# Enclosure_100x68_PBLPI.net
KiCad netlist of a schematic drawn in EAGLE
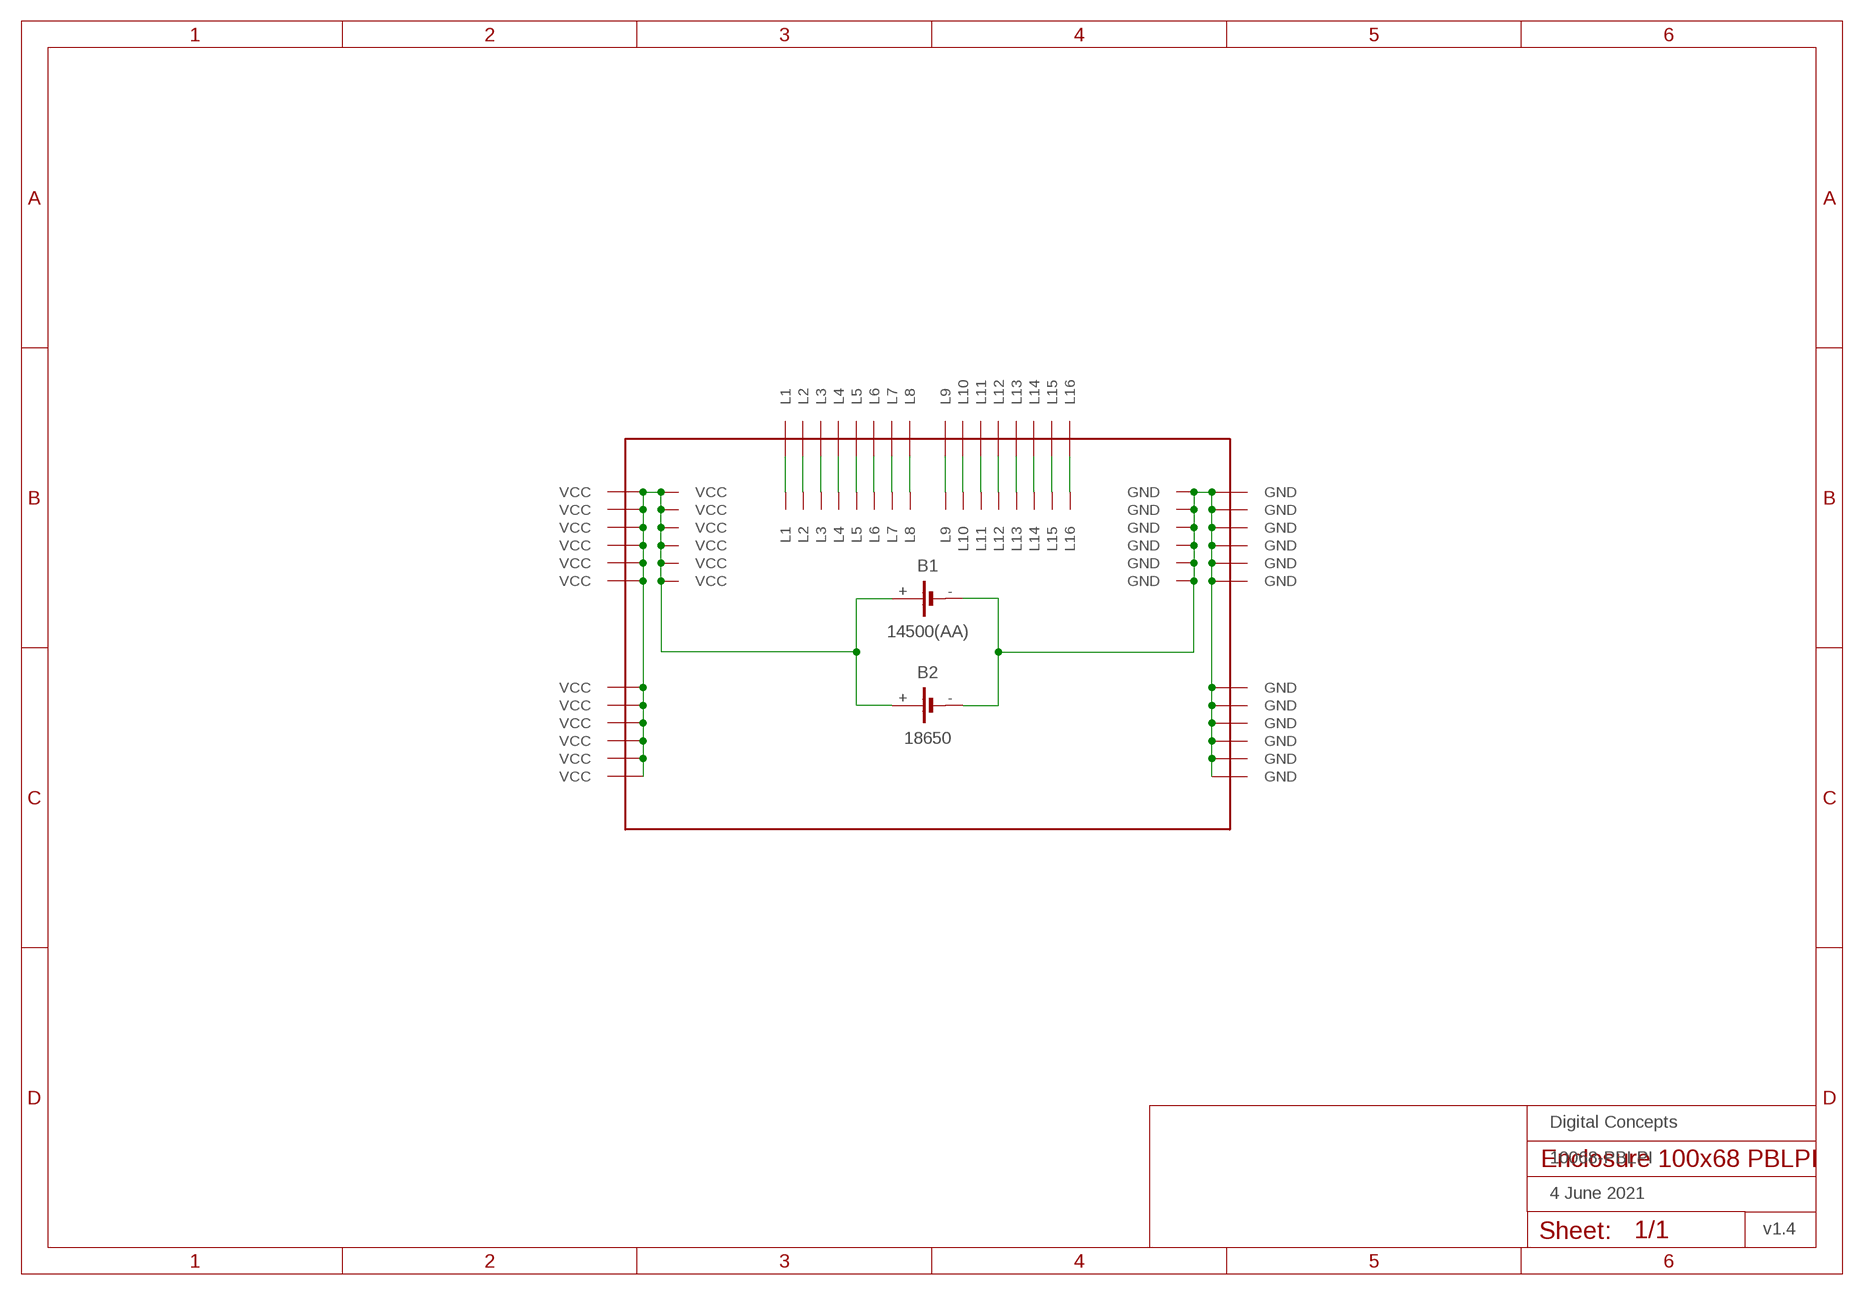
[diagram p0: schematic, sheet 1]

(export (version "E")
  (design (tool "Eeschema 10.0.6"))
  (components
    (comp (ref "B1")
      (value "14500(AA)")
      (footprint "eagle-import:BATTERY-14500")
      (libsource (lib "eagle-import") (part "BATTERY-HOLDER-14500(AA)"))
    )
    (comp (ref "B2")
      (value "18650")
      (footprint "eagle-import:BATTERY-18650")
      (libsource (lib "eagle-import") (part "BATTERY-HOLDER-18650"))
    )
    (comp (ref "P1")
      (value "PROTO-34X22-BAT-PI")
      (footprint "eagle-import:PROTO-34X22-BAT-PI")
      (libsource (lib "eagle-import") (part "PROTO-34X22-BAT-PI"))
    )
  )
  (nets
    (net (code "1") (name "Net-(B1-Pad+)") (class "Default")
      (node (ref "B1") (pin "+") (pinfunction "+_+") (pintype "power_in"))
      (node (ref "B2") (pin "+") (pinfunction "+_+") (pintype "power_in"))
      (node (ref "P1") (pin "P01-05") (pinfunction "VCC_P01-05") (pintype "power_in"))
      (node (ref "P1") (pin "P01-06") (pinfunction "VCC_P01-06") (pintype "power_in"))
      (node (ref "P1") (pin "P01-07") (pinfunction "VCC_P01-07") (pintype "power_in"))
      (node (ref "P1") (pin "P01-08") (pinfunction "VCC_P01-08") (pintype "power_in"))
      (node (ref "P1") (pin "P01-09") (pinfunction "VCC_P01-09") (pintype "power_in"))
      (node (ref "P1") (pin "P01-10") (pinfunction "VCC_P01-10") (pintype "power_in"))
      (node (ref "P1") (pin "P01-13") (pinfunction "VCC_P01-13") (pintype "power_in"))
      (node (ref "P1") (pin "P01-14") (pinfunction "VCC_P01-14") (pintype "power_in"))
      (node (ref "P1") (pin "P01-15") (pinfunction "VCC_P01-15") (pintype "power_in"))
      (node (ref "P1") (pin "P01-16") (pinfunction "VCC_P01-16") (pintype "power_in"))
      (node (ref "P1") (pin "P01-17") (pinfunction "VCC_P01-17") (pintype "power_in"))
      (node (ref "P1") (pin "P01-18") (pinfunction "VCC_P01-18") (pintype "power_in"))
      (node (ref "P1") (pin "P02-13") (pinfunction "VCC_P02-13") (pintype "power_in"))
      (node (ref "P1") (pin "P02-14") (pinfunction "VCC_P02-14") (pintype "power_in"))
      (node (ref "P1") (pin "P02-15") (pinfunction "VCC_P02-15") (pintype "power_in"))
      (node (ref "P1") (pin "P02-16") (pinfunction "VCC_P02-16") (pintype "power_in"))
      (node (ref "P1") (pin "P02-17") (pinfunction "VCC_P02-17") (pintype "power_in"))
      (node (ref "P1") (pin "P02-18") (pinfunction "VCC_P02-18") (pintype "power_in"))
    )
    (net (code "2") (name "Net-(B1-Pad-)") (class "Default")
      (node (ref "B1") (pin "-") (pinfunction "-_-") (pintype "power_in"))
      (node (ref "B2") (pin "-") (pinfunction "-_-") (pintype "power_in"))
      (node (ref "P1") (pin "P33-13") (pinfunction "GND_P33-13") (pintype "power_in"))
      (node (ref "P1") (pin "P33-14") (pinfunction "GND_P33-14") (pintype "power_in"))
      (node (ref "P1") (pin "P33-15") (pinfunction "GND_P33-15") (pintype "power_in"))
      (node (ref "P1") (pin "P33-16") (pinfunction "GND_P33-16") (pintype "power_in"))
      (node (ref "P1") (pin "P33-17") (pinfunction "GND_P33-17") (pintype "power_in"))
      (node (ref "P1") (pin "P33-18") (pinfunction "GND_P33-18") (pintype "power_in"))
      (node (ref "P1") (pin "P34-05") (pinfunction "GND_P34-05") (pintype "power_in"))
      (node (ref "P1") (pin "P34-06") (pinfunction "GND_P34-06") (pintype "power_in"))
      (node (ref "P1") (pin "P34-07") (pinfunction "GND_P34-07") (pintype "power_in"))
      (node (ref "P1") (pin "P34-08") (pinfunction "GND_P34-08") (pintype "power_in"))
      (node (ref "P1") (pin "P34-09") (pinfunction "GND_P34-09") (pintype "power_in"))
      (node (ref "P1") (pin "P34-10") (pinfunction "GND_P34-10") (pintype "power_in"))
      (node (ref "P1") (pin "P34-13") (pinfunction "GND_P34-13") (pintype "power_in"))
      (node (ref "P1") (pin "P34-14") (pinfunction "GND_P34-14") (pintype "power_in"))
      (node (ref "P1") (pin "P34-15") (pinfunction "GND_P34-15") (pintype "power_in"))
      (node (ref "P1") (pin "P34-16") (pinfunction "GND_P34-16") (pintype "power_in"))
      (node (ref "P1") (pin "P34-17") (pinfunction "GND_P34-17") (pintype "power_in"))
      (node (ref "P1") (pin "P34-18") (pinfunction "GND_P34-18") (pintype "power_in"))
    )
    (net (code "3") (name "Net-(P1-L1-PadP10-21)") (class "Default")
      (node (ref "P1") (pin "P10-21") (pinfunction "L1_P10-21") (pintype "passive"))
      (node (ref "P1") (pin "P10-22") (pinfunction "L1_P10-22") (pintype "passive"))
    )
    (net (code "4") (name "Net-(P1-L2-PadP11-21)") (class "Default")
      (node (ref "P1") (pin "P11-21") (pinfunction "L2_P11-21") (pintype "passive"))
      (node (ref "P1") (pin "P11-22") (pinfunction "L2_P11-22") (pintype "passive"))
    )
    (net (code "5") (name "Net-(P1-L3-PadP12-21)") (class "Default")
      (node (ref "P1") (pin "P12-21") (pinfunction "L3_P12-21") (pintype "passive"))
      (node (ref "P1") (pin "P12-22") (pinfunction "L3_P12-22") (pintype "passive"))
    )
    (net (code "6") (name "Net-(P1-L4-PadP13-21)") (class "Default")
      (node (ref "P1") (pin "P13-21") (pinfunction "L4_P13-21") (pintype "passive"))
      (node (ref "P1") (pin "P13-22") (pinfunction "L4_P13-22") (pintype "passive"))
    )
    (net (code "7") (name "Net-(P1-L5-PadP14-21)") (class "Default")
      (node (ref "P1") (pin "P14-21") (pinfunction "L5_P14-21") (pintype "passive"))
      (node (ref "P1") (pin "P14-22") (pinfunction "L5_P14-22") (pintype "passive"))
    )
    (net (code "8") (name "Net-(P1-L6-PadP15-21)") (class "Default")
      (node (ref "P1") (pin "P15-21") (pinfunction "L6_P15-21") (pintype "passive"))
      (node (ref "P1") (pin "P15-22") (pinfunction "L6_P15-22") (pintype "passive"))
    )
    (net (code "9") (name "Net-(P1-L7-PadP16-21)") (class "Default")
      (node (ref "P1") (pin "P16-21") (pinfunction "L7_P16-21") (pintype "passive"))
      (node (ref "P1") (pin "P16-22") (pinfunction "L7_P16-22") (pintype "passive"))
    )
    (net (code "10") (name "Net-(P1-L8-PadP17-21)") (class "Default")
      (node (ref "P1") (pin "P17-21") (pinfunction "L8_P17-21") (pintype "passive"))
      (node (ref "P1") (pin "P17-22") (pinfunction "L8_P17-22") (pintype "passive"))
    )
    (net (code "11") (name "Net-(P1-L9-PadP18-21)") (class "Default")
      (node (ref "P1") (pin "P18-21") (pinfunction "L9_P18-21") (pintype "passive"))
      (node (ref "P1") (pin "P18-22") (pinfunction "L9_P18-22") (pintype "passive"))
    )
    (net (code "12") (name "Net-(P1-L10-PadP19-21)") (class "Default")
      (node (ref "P1") (pin "P19-21") (pinfunction "L10_P19-21") (pintype "passive"))
      (node (ref "P1") (pin "P19-22") (pinfunction "L10_P19-22") (pintype "passive"))
    )
    (net (code "13") (name "Net-(P1-L11-PadP20-21)") (class "Default")
      (node (ref "P1") (pin "P20-21") (pinfunction "L11_P20-21") (pintype "passive"))
      (node (ref "P1") (pin "P20-22") (pinfunction "L11_P20-22") (pintype "passive"))
    )
    (net (code "14") (name "Net-(P1-L12-PadP21-21)") (class "Default")
      (node (ref "P1") (pin "P21-21") (pinfunction "L12_P21-21") (pintype "passive"))
      (node (ref "P1") (pin "P21-22") (pinfunction "L12_P21-22") (pintype "passive"))
    )
    (net (code "15") (name "Net-(P1-L13-PadP22-21)") (class "Default")
      (node (ref "P1") (pin "P22-21") (pinfunction "L13_P22-21") (pintype "passive"))
      (node (ref "P1") (pin "P22-22") (pinfunction "L13_P22-22") (pintype "passive"))
    )
    (net (code "16") (name "Net-(P1-L14-PadP23-21)") (class "Default")
      (node (ref "P1") (pin "P23-21") (pinfunction "L14_P23-21") (pintype "passive"))
      (node (ref "P1") (pin "P23-22") (pinfunction "L14_P23-22") (pintype "passive"))
    )
    (net (code "17") (name "Net-(P1-L15-PadP24-21)") (class "Default")
      (node (ref "P1") (pin "P24-21") (pinfunction "L15_P24-21") (pintype "passive"))
      (node (ref "P1") (pin "P24-22") (pinfunction "L15_P24-22") (pintype "passive"))
    )
    (net (code "18") (name "Net-(P1-L16-PadP25-21)") (class "Default")
      (node (ref "P1") (pin "P25-21") (pinfunction "L16_P25-21") (pintype "passive"))
      (node (ref "P1") (pin "P25-22") (pinfunction "L16_P25-22") (pintype "passive"))
    )
  )
)
